# GLCD.net
KiCad netlist of a schematic drawn in Altium Designer
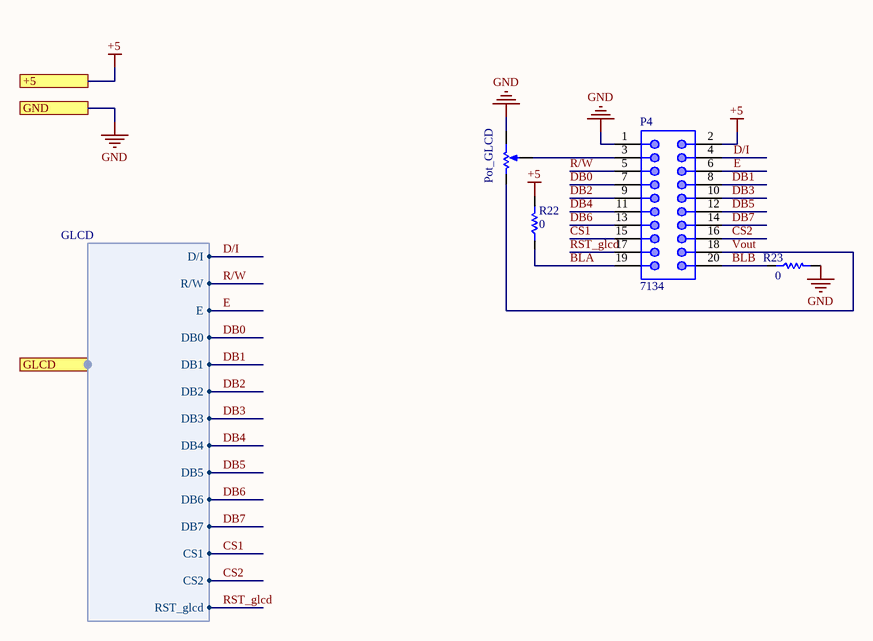
[diagram p0: GLCD.SchDoc]

(export (version "E")
  (design (tool "Eeschema 10.0.6"))
  (components
    (comp (ref "P4")
      (value "10x2")
      (footprint "BOX-HDR-10X2-2.54mm-S")
      (description "Male Box Header, 20 pins")
      (fields (field (name "INFLOW") "7134") (field (name "VALIDATION") "NT"))
      (libsource (lib "aKaReZa") (part "Con_IDC_10x2"))
    )
    (comp (ref "Pot_GLCD")
      (value "10K")
      (footprint "Multi turn 01")
      (description "Multi Turn")
      (fields (field (name "VALIDATION") "Valid"))
      (libsource (lib "aKaReZa") (part "Res_Multi"))
    )
    (comp (ref "R22")
      (value "0")
      (footprint "RES 1206 (3216X08L)")
      (description "Resistor")
      (fields (field (name "VALIDATION") "Valid"))
      (libsource (lib "aKaReZa") (part "Res_SMD_1206"))
    )
    (comp (ref "R23")
      (value "0")
      (footprint "RES 1206 (3216X08L)")
      (description "Resistor")
      (fields (field (name "VALIDATION") "Valid"))
      (libsource (lib "aKaReZa") (part "Res_SMD_1206"))
    )
  )
  (nets
    (net (code "2") (name "+5") (class "Default")
      (node (ref "P4") (pin "2") (pinfunction "2_2") (pintype "passive"))
      (node (ref "R22") (pin "2") (pinfunction "2_2") (pintype "passive"))
    )
    (net (code "3") (name "/BLA") (class "Default")
      (node (ref "P4") (pin "19") (pinfunction "19_19") (pintype "passive"))
      (node (ref "R22") (pin "1") (pinfunction "1_1") (pintype "passive"))
    )
    (net (code "4") (name "/BLB") (class "Default")
      (node (ref "P4") (pin "20") (pinfunction "20_20") (pintype "passive"))
      (node (ref "R23") (pin "1") (pinfunction "1_1") (pintype "passive"))
    )
    (net (code "5") (name "/CS1") (class "Default")
      (node (ref "P4") (pin "15") (pinfunction "15_15") (pintype "passive"))
    )
    (net (code "6") (name "/CS2") (class "Default")
      (node (ref "P4") (pin "16") (pinfunction "16_16") (pintype "passive"))
    )
    (net (code "7") (name "/DB0") (class "Default")
      (node (ref "P4") (pin "7") (pinfunction "7_7") (pintype "passive"))
    )
    (net (code "8") (name "/DB1") (class "Default")
      (node (ref "P4") (pin "8") (pinfunction "8_8") (pintype "passive"))
    )
    (net (code "9") (name "/DB2") (class "Default")
      (node (ref "P4") (pin "9") (pinfunction "9_9") (pintype "passive"))
    )
    (net (code "10") (name "/DB3") (class "Default")
      (node (ref "P4") (pin "10") (pinfunction "10_10") (pintype "passive"))
    )
    (net (code "11") (name "/DB4") (class "Default")
      (node (ref "P4") (pin "11") (pinfunction "11_11") (pintype "passive"))
    )
    (net (code "12") (name "/DB5") (class "Default")
      (node (ref "P4") (pin "12") (pinfunction "12_12") (pintype "passive"))
    )
    (net (code "13") (name "/DB6") (class "Default")
      (node (ref "P4") (pin "13") (pinfunction "13_13") (pintype "passive"))
    )
    (net (code "14") (name "/DB7") (class "Default")
      (node (ref "P4") (pin "14") (pinfunction "14_14") (pintype "passive"))
    )
    (net (code "15") (name "/D{slash}I") (class "Default")
      (node (ref "P4") (pin "4") (pinfunction "4_4") (pintype "passive"))
    )
    (net (code "16") (name "/E") (class "Default")
      (node (ref "P4") (pin "6") (pinfunction "6_6") (pintype "passive"))
    )
    (net (code "17") (name "/RST_glcd") (class "Default")
      (node (ref "P4") (pin "17") (pinfunction "17_17") (pintype "passive"))
    )
    (net (code "18") (name "/R{slash}W") (class "Default")
      (node (ref "P4") (pin "5") (pinfunction "5_5") (pintype "passive"))
    )
    (net (code "19") (name "/Vout") (class "Default")
      (node (ref "P4") (pin "18") (pinfunction "18_18") (pintype "passive"))
      (node (ref "Pot_GLCD") (pin "3") (pinfunction "1_3") (pintype "passive"))
    )
    (net (code "21") (name "GND") (class "Default")
      (node (ref "P4") (pin "1") (pinfunction "1_1") (pintype "passive"))
      (node (ref "Pot_GLCD") (pin "1") (pinfunction "3_1") (pintype "passive"))
      (node (ref "R23") (pin "2") (pinfunction "2_2") (pintype "passive"))
    )
    (net (code "22") (name "Net-(P4-Pad3)") (class "Default")
      (node (ref "P4") (pin "3") (pinfunction "3_3") (pintype "passive"))
      (node (ref "Pot_GLCD") (pin "2") (pinfunction "2_2") (pintype "passive"))
    )
  )
)
